# Amplifier.net
KiCad netlist of a schematic drawn in Altium Designer
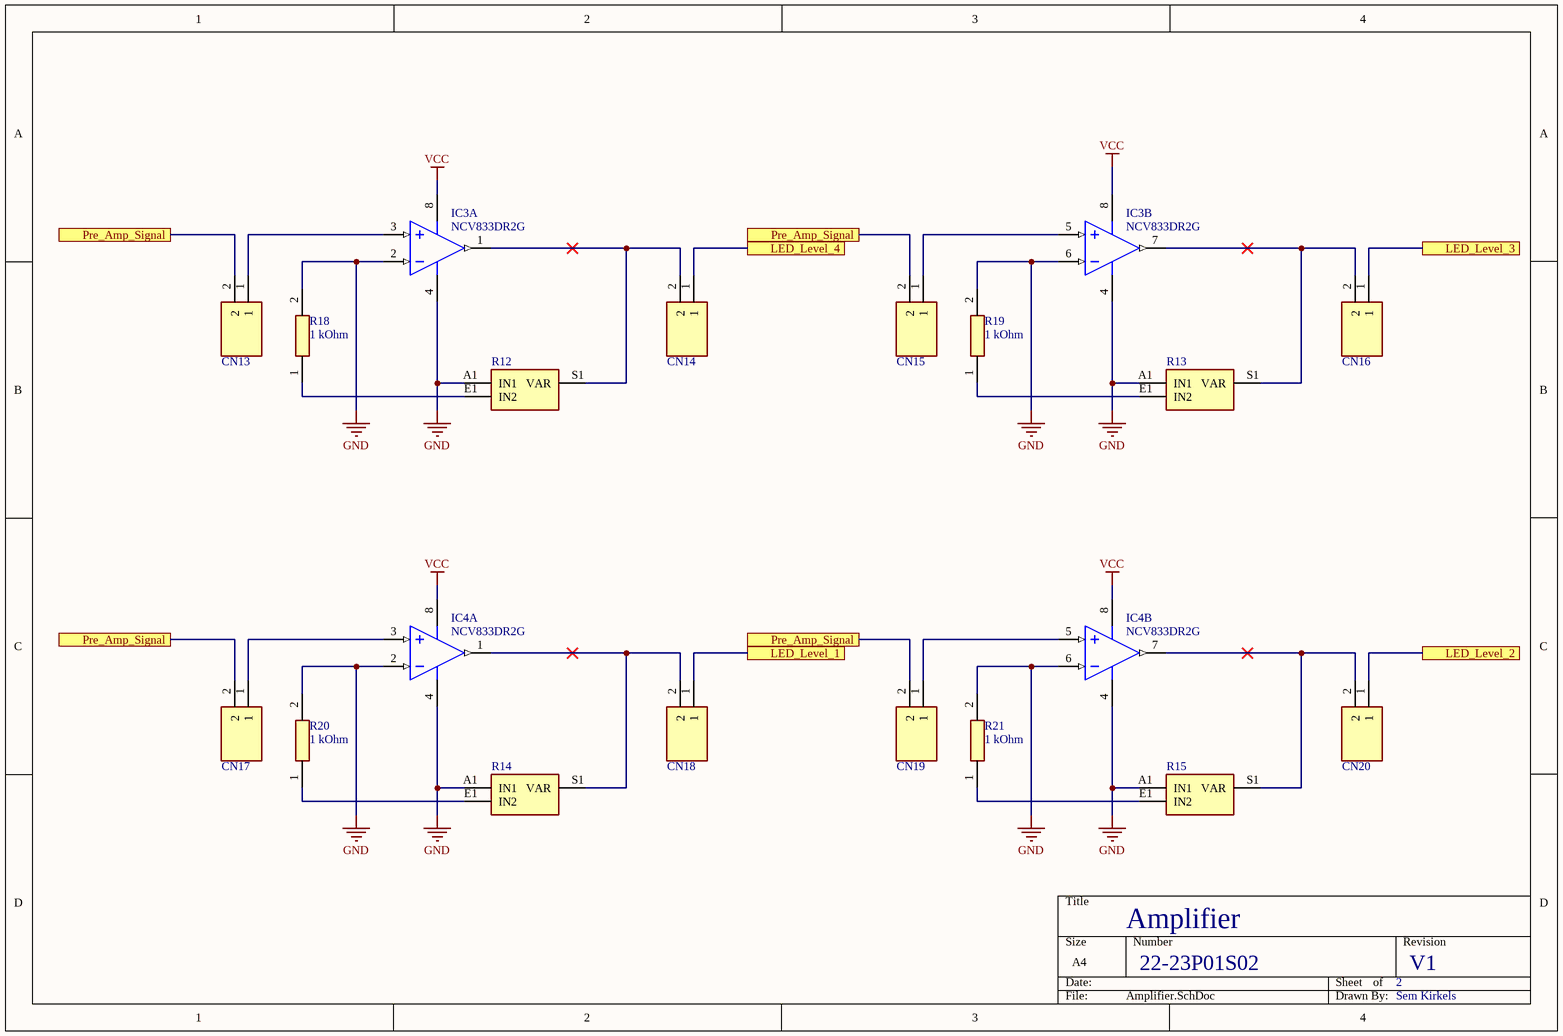
[diagram p0: Amplifier.SchDoc]

(export (version "E")
  (design (tool "Eeschema 10.0.6"))
  (components
    (comp (ref "CN13")
      (value "2 Pin Header")
      (footprint "2 Pin Header")
      (description "Connector")
      (fields
        (field (name "MANUFACTURER_PART_NUMBER") "5-146284-2")
        (field (name "MOUSER PART NUMBER") "571-5-146284-2")
      )
      (libsource (lib "IR_Communication_Schematic_Lib") (part "2 Pin Header"))
    )
    (comp (ref "CN14")
      (value "2 Pin Header")
      (footprint "2 Pin Header")
      (description "Connector")
      (fields
        (field (name "MANUFACTURER_PART_NUMBER") "5-146284-2")
        (field (name "MOUSER PART NUMBER") "571-5-146284-2")
      )
      (libsource (lib "IR_Communication_Schematic_Lib") (part "2 Pin Header"))
    )
    (comp (ref "CN15")
      (value "2 Pin Header")
      (footprint "2 Pin Header")
      (description "Connector")
      (fields
        (field (name "MANUFACTURER_PART_NUMBER") "5-146284-2")
        (field (name "MOUSER PART NUMBER") "571-5-146284-2")
      )
      (libsource (lib "IR_Communication_Schematic_Lib") (part "2 Pin Header"))
    )
    (comp (ref "CN16")
      (value "2 Pin Header")
      (footprint "2 Pin Header")
      (description "Connector")
      (fields
        (field (name "MANUFACTURER_PART_NUMBER") "5-146284-2")
        (field (name "MOUSER PART NUMBER") "571-5-146284-2")
      )
      (libsource (lib "IR_Communication_Schematic_Lib") (part "2 Pin Header"))
    )
    (comp (ref "CN17")
      (value "2 Pin Header")
      (footprint "2 Pin Header")
      (description "Connector")
      (fields
        (field (name "MANUFACTURER_PART_NUMBER") "5-146284-2")
        (field (name "MOUSER PART NUMBER") "571-5-146284-2")
      )
      (libsource (lib "IR_Communication_Schematic_Lib") (part "2 Pin Header"))
    )
    (comp (ref "CN18")
      (value "2 Pin Header")
      (footprint "2 Pin Header")
      (description "Connector")
      (fields
        (field (name "MANUFACTURER_PART_NUMBER") "5-146284-2")
        (field (name "MOUSER PART NUMBER") "571-5-146284-2")
      )
      (libsource (lib "IR_Communication_Schematic_Lib") (part "2 Pin Header"))
    )
    (comp (ref "CN19")
      (value "2 Pin Header")
      (footprint "2 Pin Header")
      (description "Connector")
      (fields
        (field (name "MANUFACTURER_PART_NUMBER") "5-146284-2")
        (field (name "MOUSER PART NUMBER") "571-5-146284-2")
      )
      (libsource (lib "IR_Communication_Schematic_Lib") (part "2 Pin Header"))
    )
    (comp (ref "CN20")
      (value "2 Pin Header")
      (footprint "2 Pin Header")
      (description "Connector")
      (fields
        (field (name "MANUFACTURER_PART_NUMBER") "5-146284-2")
        (field (name "MOUSER PART NUMBER") "571-5-146284-2")
      )
      (libsource (lib "IR_Communication_Schematic_Lib") (part "2 Pin Header"))
    )
    (comp (ref "IC3")
      (value "NCV833DR2G")
      (footprint "Footprint Opamp")
      (description "Low Noise, Audio Dual Operational Amplifier, -40 to 85 degC, 8-Pin SOIC, Pb-Free, Tape and Reel")
      (fields (field (name "MANUFACTURER") "On Semiconductor"))
      (libsource (lib "IR_Communication_Schematic_Lib") (part "Opamp"))
    )
    (comp (ref "IC4")
      (value "NCV833DR2G")
      (footprint "Footprint Opamp")
      (description "Low Noise, Audio Dual Operational Amplifier, -40 to 85 degC, 8-Pin SOIC, Pb-Free, Tape and Reel")
      (fields (field (name "MANUFACTURER") "On Semiconductor"))
      (libsource (lib "IR_Communication_Schematic_Lib") (part "Opamp"))
    )
    (comp (ref "R12")
      (value "PT10LV10-202A2020-S")
      (footprint "Variable resistor")
      (description "Variable Resistor")
      (fields (field (name "MOUSER PART NUMBER") "531-PT10V-2K-S"))
      (libsource (lib "IR_Communication_Schematic_Lib") (part "PT10LV10-202A2020-S"))
    )
    (comp (ref "R13")
      (value "PT10LV10-202A2020-S")
      (footprint "Variable resistor")
      (description "Variable Resistor")
      (fields (field (name "MOUSER PART NUMBER") "531-PT10V-2K-S"))
      (libsource (lib "IR_Communication_Schematic_Lib") (part "PT10LV10-202A2020-S"))
    )
    (comp (ref "R14")
      (value "PT10LV10-202A2020-S")
      (footprint "Variable resistor")
      (description "Variable Resistor")
      (fields (field (name "MOUSER PART NUMBER") "531-PT10V-2K-S"))
      (libsource (lib "IR_Communication_Schematic_Lib") (part "PT10LV10-202A2020-S"))
    )
    (comp (ref "R15")
      (value "PT10LV10-202A2020-S")
      (footprint "Variable resistor")
      (description "Variable Resistor")
      (fields (field (name "MOUSER PART NUMBER") "531-PT10V-2K-S"))
      (libsource (lib "IR_Communication_Schematic_Lib") (part "PT10LV10-202A2020-S"))
    )
    (comp (ref "R18")
      (value "1 kOhm")
      (footprint "0805")
      (description "Resistor")
      (fields
        (field (name "MANUFACTURER_PART_NUMBER") "RP0805BRD071KL")
        (field (name "MOUSER PART NUMBER") "603-RP0805BRD071KL")
      )
      (libsource (lib "IR_Communication_Schematic_Lib") (part "Resistor"))
    )
    (comp (ref "R19")
      (value "1 kOhm")
      (footprint "0805")
      (description "Resistor")
      (fields
        (field (name "MANUFACTURER_PART_NUMBER") "RP0805BRD071KL")
        (field (name "MOUSER PART NUMBER") "603-RP0805BRD071KL")
      )
      (libsource (lib "IR_Communication_Schematic_Lib") (part "Resistor"))
    )
    (comp (ref "R20")
      (value "1 kOhm")
      (footprint "0805")
      (description "Resistor")
      (fields
        (field (name "MANUFACTURER_PART_NUMBER") "RP0805BRD071KL")
        (field (name "MOUSER PART NUMBER") "603-RP0805BRD071KL")
      )
      (libsource (lib "IR_Communication_Schematic_Lib") (part "Resistor"))
    )
    (comp (ref "R21")
      (value "1 kOhm")
      (footprint "0805")
      (description "Resistor")
      (fields
        (field (name "MANUFACTURER_PART_NUMBER") "RP0805BRD071KL")
        (field (name "MOUSER PART NUMBER") "603-RP0805BRD071KL")
      )
      (libsource (lib "IR_Communication_Schematic_Lib") (part "Resistor"))
    )
  )
  (nets
    (net (code "1") (name "/LED_Level_1") (class "Default")
      (node (ref "CN18") (pin "1") (pinfunction "1_1") (pintype "passive"))
    )
    (net (code "2") (name "/LED_Level_2") (class "Default")
      (node (ref "CN20") (pin "1") (pinfunction "1_1") (pintype "passive"))
    )
    (net (code "3") (name "/LED_Level_3") (class "Default")
      (node (ref "CN16") (pin "1") (pinfunction "1_1") (pintype "passive"))
    )
    (net (code "4") (name "/LED_Level_4") (class "Default")
      (node (ref "CN14") (pin "1") (pinfunction "1_1") (pintype "passive"))
    )
    (net (code "5") (name "/Pre_Amp_Signal") (class "Default")
      (node (ref "CN13") (pin "2") (pinfunction "2_2") (pintype "passive"))
      (node (ref "CN15") (pin "2") (pinfunction "2_2") (pintype "passive"))
      (node (ref "CN17") (pin "2") (pinfunction "2_2") (pintype "passive"))
      (node (ref "CN19") (pin "2") (pinfunction "2_2") (pintype "passive"))
    )
    (net (code "6") (name "GND") (class "Default")
      (node (ref "IC3") (pin "2") (pinfunction "IN1-_2") (pintype "input"))
      (node (ref "IC3") (pin "4") (pinfunction "VEE_4") (pintype "power_in"))
      (node (ref "IC3") (pin "6") (pinfunction "IN2-_6") (pintype "input"))
      (node (ref "IC4") (pin "2") (pinfunction "IN1-_2") (pintype "input"))
      (node (ref "IC4") (pin "4") (pinfunction "VEE_4") (pintype "power_in"))
      (node (ref "IC4") (pin "6") (pinfunction "IN2-_6") (pintype "input"))
      (node (ref "R12") (pin "A1") (pinfunction "IN1_A1") (pintype "passive"))
      (node (ref "R13") (pin "A1") (pinfunction "IN1_A1") (pintype "passive"))
      (node (ref "R14") (pin "A1") (pinfunction "IN1_A1") (pintype "passive"))
      (node (ref "R15") (pin "A1") (pinfunction "IN1_A1") (pintype "passive"))
      (node (ref "R18") (pin "2") (pinfunction "2_2") (pintype "passive"))
      (node (ref "R19") (pin "2") (pinfunction "2_2") (pintype "passive"))
      (node (ref "R20") (pin "2") (pinfunction "2_2") (pintype "passive"))
      (node (ref "R21") (pin "2") (pinfunction "2_2") (pintype "passive"))
    )
    (net (code "7") (name "Net-(IC3A-IN1+)") (class "Default")
      (node (ref "CN13") (pin "1") (pinfunction "1_1") (pintype "passive"))
      (node (ref "IC3") (pin "3") (pinfunction "IN1+_3") (pintype "input"))
    )
    (net (code "8") (name "Net-(IC3A-OUT1)") (class "Default")
      (node (ref "CN14") (pin "2") (pinfunction "2_2") (pintype "passive"))
      (node (ref "IC3") (pin "1") (pinfunction "OUT1_1") (pintype "output"))
      (node (ref "R12") (pin "S1") (pinfunction "VAR_S1") (pintype "passive"))
    )
    (net (code "9") (name "Net-(IC3B-IN2+)") (class "Default")
      (node (ref "CN15") (pin "1") (pinfunction "1_1") (pintype "passive"))
      (node (ref "IC3") (pin "5") (pinfunction "IN2+_5") (pintype "input"))
    )
    (net (code "10") (name "Net-(IC3B-OUT2)") (class "Default")
      (node (ref "CN16") (pin "2") (pinfunction "2_2") (pintype "passive"))
      (node (ref "IC3") (pin "7") (pinfunction "OUT2_7") (pintype "output"))
      (node (ref "R13") (pin "S1") (pinfunction "VAR_S1") (pintype "passive"))
    )
    (net (code "11") (name "Net-(IC4A-IN1+)") (class "Default")
      (node (ref "CN17") (pin "1") (pinfunction "1_1") (pintype "passive"))
      (node (ref "IC4") (pin "3") (pinfunction "IN1+_3") (pintype "input"))
    )
    (net (code "12") (name "Net-(IC4A-OUT1)") (class "Default")
      (node (ref "CN18") (pin "2") (pinfunction "2_2") (pintype "passive"))
      (node (ref "IC4") (pin "1") (pinfunction "OUT1_1") (pintype "output"))
      (node (ref "R14") (pin "S1") (pinfunction "VAR_S1") (pintype "passive"))
    )
    (net (code "13") (name "Net-(IC4B-IN2+)") (class "Default")
      (node (ref "CN19") (pin "1") (pinfunction "1_1") (pintype "passive"))
      (node (ref "IC4") (pin "5") (pinfunction "IN2+_5") (pintype "input"))
    )
    (net (code "14") (name "Net-(IC4B-OUT2)") (class "Default")
      (node (ref "CN20") (pin "2") (pinfunction "2_2") (pintype "passive"))
      (node (ref "IC4") (pin "7") (pinfunction "OUT2_7") (pintype "output"))
      (node (ref "R15") (pin "S1") (pinfunction "VAR_S1") (pintype "passive"))
    )
    (net (code "15") (name "Net-(R12-IN2)") (class "Default")
      (node (ref "R12") (pin "E1") (pinfunction "IN2_E1") (pintype "passive"))
      (node (ref "R18") (pin "1") (pinfunction "1_1") (pintype "passive"))
    )
    (net (code "16") (name "Net-(R13-IN2)") (class "Default")
      (node (ref "R13") (pin "E1") (pinfunction "IN2_E1") (pintype "passive"))
      (node (ref "R19") (pin "1") (pinfunction "1_1") (pintype "passive"))
    )
    (net (code "17") (name "Net-(R14-IN2)") (class "Default")
      (node (ref "R14") (pin "E1") (pinfunction "IN2_E1") (pintype "passive"))
      (node (ref "R20") (pin "1") (pinfunction "1_1") (pintype "passive"))
    )
    (net (code "18") (name "Net-(R15-IN2)") (class "Default")
      (node (ref "R15") (pin "E1") (pinfunction "IN2_E1") (pintype "passive"))
      (node (ref "R21") (pin "1") (pinfunction "1_1") (pintype "passive"))
    )
    (net (code "19") (name "VCC") (class "Default")
      (node (ref "IC3") (pin "8") (pinfunction "VCC_8") (pintype "power_in"))
      (node (ref "IC4") (pin "8") (pinfunction "VCC_8") (pintype "power_in"))
    )
  )
)
